# Power.net
KiCad netlist of a schematic drawn in Altium Designer
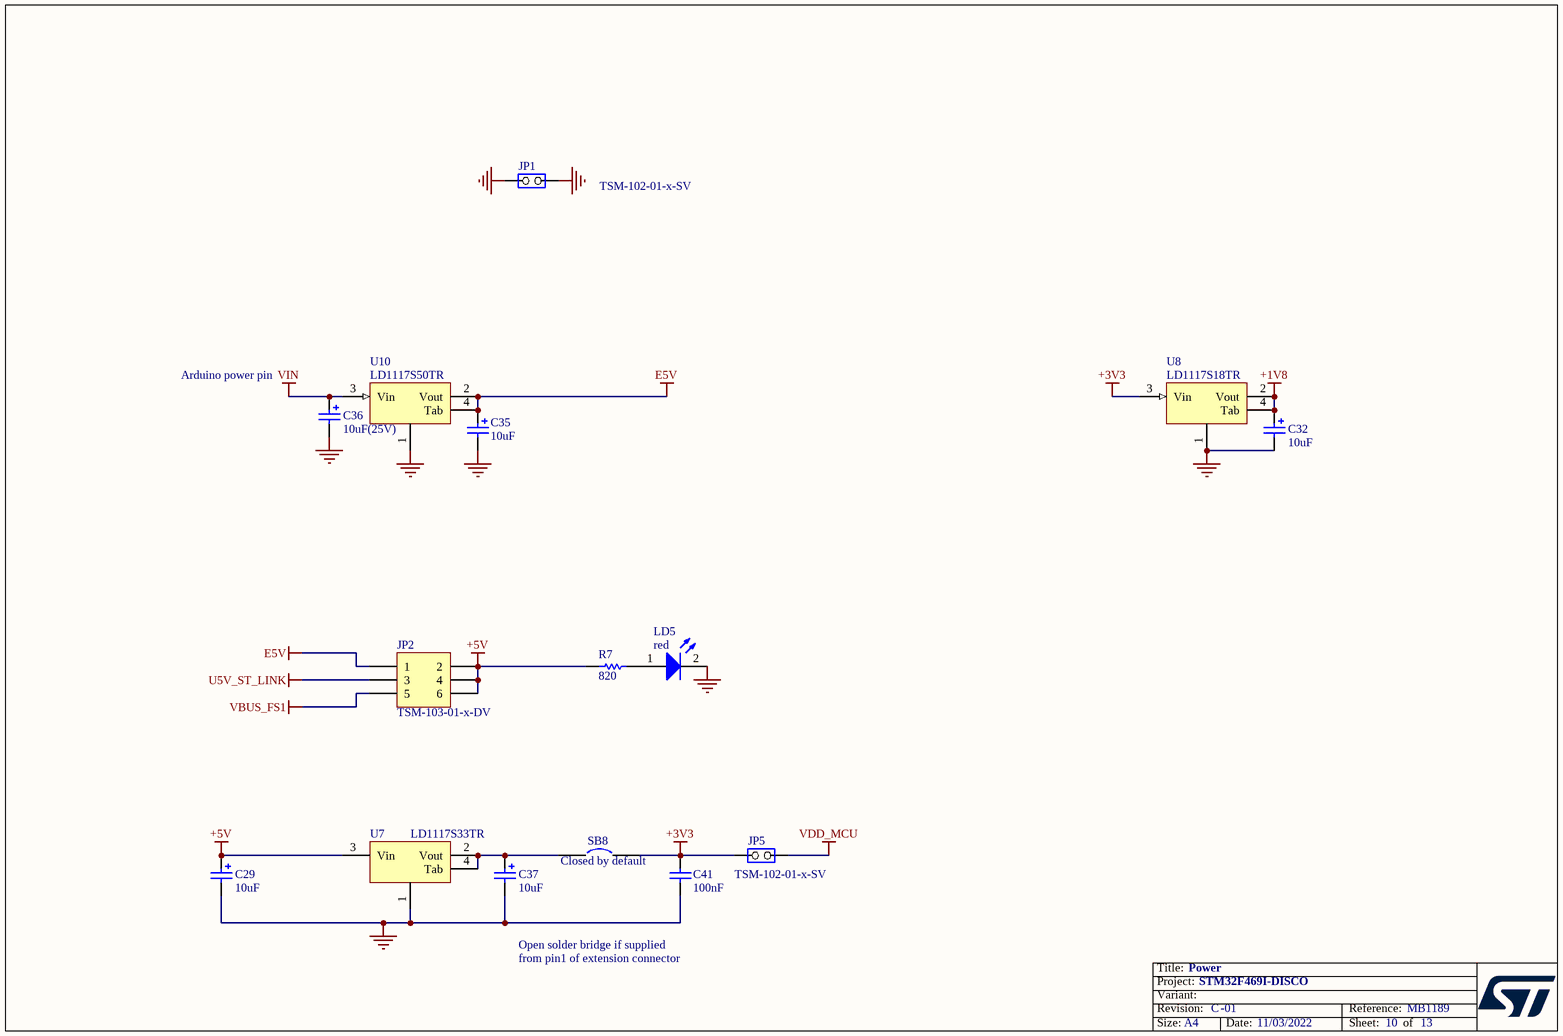
[diagram p0: Power.SchDoc]

(export (version "E")
  (design (tool "Eeschema 10.0.6"))
  (components
    (comp (ref "C29")
      (value "10uF")
      (footprint "CPOL_TAJ-A_1206_H180")
      (description "Capacitor, Tantalum, 10uF, 16V, 10%, 3Ohms, pkg Type_A (3216 metric), T=1.6mm")
      (libsource (lib "MB1189") (part "Cap_TAJA106K016R"))
    )
    (comp (ref "C32")
      (value "10uF")
      (footprint "CPOL_TAJ-A_1206_H180")
      (description "Capacitor, Tantalum, 10uF, 16V, 10%, 3Ohms, pkg Type_A (3216 metric), T=1.6mm")
      (libsource (lib "MB1189") (part "Cap_TAJA106K016R"))
    )
    (comp (ref "C35")
      (value "10uF")
      (footprint "CPOL_TAJ-A_1206_H180")
      (description "Capacitor, Tantalum, 10uF, 16V, 10%, 3Ohms, pkg Type_A (3216 metric), T=1.6mm")
      (libsource (lib "MB1189") (part "Cap_TAJA106K016R"))
    )
    (comp (ref "C36")
      (value "10uF(25V)")
      (footprint "CPOL_TAJ-B_1210_H210")
      (description "Capacitor, Tantalum, 10uF, 25V, 10%, 2.5ohms, pkg Type_B (3528 metric), T=1.9mm")
      (libsource (lib "MB1189") (part "Cap_TAJB106K025RNJ"))
    )
    (comp (ref "C37")
      (value "10uF")
      (footprint "CPOL_TAJ-A_1206_H180")
      (description "Capacitor, Tantalum, 10uF, 16V, 10%, 3Ohms, pkg Type_A (3216 metric), T=1.6mm")
      (libsource (lib "MB1189") (part "Cap_TAJA106K016R"))
    )
    (comp (ref "C41")
      (value "100nF")
      (footprint "0402C")
      (description "Capacitor")
      (fields (field (name "PUBLISHER") "Altium Limited"))
      (libsource (lib "Miscellaneous Devices") (part "Cap"))
    )
    (comp (ref "JP1")
      (value "TSM-102-01-x-SV")
      (footprint "TSM-102-01-x-SV")
      (libsource (lib "*") (part "JP2"))
    )
    (comp (ref "JP2")
      (value "TSM-103-01-x-DV")
      (footprint "TSM-103-01-x-DV")
      (description "Header, 3-Pin, Dual row")
      (fields (field (name "PUBLISHER") "Altium Limited"))
      (libsource (lib "Miscellaneous Connectors") (part "Header 3X2"))
    )
    (comp (ref "JP5")
      (value "TSM-102-01-x-SV")
      (footprint "TSM-102-01-x-SV")
      (libsource (lib "*") (part "JP2"))
    )
    (comp (ref "LD5")
      (value "red")
      (footprint "0603D")
      (description "Typical RED, GREEN, YELLOW, AMBER GaAs LED")
      (fields (field (name "PUBLISHER") "Altium Limited"))
      (libsource (lib "Miscellaneous Devices") (part "LED2"))
    )
    (comp (ref "R7")
      (value "820")
      (footprint "0603R")
      (description "Resistor")
      (fields (field (name "PUBLISHER") "Altium Limited"))
      (libsource (lib "Miscellaneous Devices") (part "res1"))
    )
    (comp (ref "SB8")
      (value "Closed by default")
      (footprint "SB_0603")
      (description "Circuit Breaker")
      (fields (field (name "PUBLISHER") "Altium Limited"))
      (libsource (lib "Miscellaneous Devices") (part "Circuit Breaker"))
    )
    (comp (ref "U7")
      (value "LD1117S33TR")
      (footprint "SOT-223")
      (description "LOW DROP FIXED AND ADJUSTABLE POSITIVE VOLTAGE REGULATORS (3.3 Volts)")
      (libsource (lib "MCD_TOOLS") (part "LD1117S33TR"))
    )
    (comp (ref "U8") (value "LD1117S18TR") (footprint "SOT-223") (libsource (lib "mb1045") (part "LD1117")))
    (comp (ref "U10") (value "LD1117S50TR") (footprint "SOT-223") (libsource (lib "mb1045") (part "LD1117")))
  )
  (nets
    (net (code "1") (name "+1V8") (class "Default")
      (node (ref "C32") (pin "1") (pinfunction "1_1") (pintype "passive"))
      (node (ref "U8") (pin "2") (pinfunction "Vout_2") (pintype "power_in"))
      (node (ref "U8") (pin "4") (pinfunction "Tab_4") (pintype "power_in"))
    )
    (net (code "2") (name "+3V3") (class "Default")
      (node (ref "C41") (pin "1") (pinfunction "1_1") (pintype "passive"))
      (node (ref "JP5") (pin "1") (pinfunction "COMMON_1") (pintype "passive"))
      (node (ref "SB8") (pin "2") (pinfunction "2_2") (pintype "passive"))
      (node (ref "U8") (pin "3") (pinfunction "Vin_3") (pintype "input"))
    )
    (net (code "3") (name "+5V") (class "Default")
      (node (ref "C29") (pin "1") (pinfunction "1_1") (pintype "passive"))
      (node (ref "JP2") (pin "2") (pinfunction "2_2") (pintype "passive"))
      (node (ref "JP2") (pin "4") (pinfunction "4_4") (pintype "passive"))
      (node (ref "JP2") (pin "6") (pinfunction "6_6") (pintype "passive"))
      (node (ref "R7") (pin "2") (pinfunction "2_2") (pintype "passive"))
      (node (ref "U7") (pin "3") (pinfunction "Vin_3") (pintype "passive"))
    )
    (net (code "4") (name "E5V") (class "Default")
      (node (ref "C35") (pin "1") (pinfunction "1_1") (pintype "passive"))
      (node (ref "JP2") (pin "1") (pinfunction "1_1") (pintype "passive"))
      (node (ref "U10") (pin "2") (pinfunction "Vout_2") (pintype "power_in"))
      (node (ref "U10") (pin "4") (pinfunction "Tab_4") (pintype "power_in"))
    )
    (net (code "5") (name "GND") (class "Default")
      (node (ref "C29") (pin "2") (pinfunction "2_2") (pintype "passive"))
      (node (ref "C32") (pin "2") (pinfunction "2_2") (pintype "passive"))
      (node (ref "C35") (pin "2") (pinfunction "2_2") (pintype "passive"))
      (node (ref "C36") (pin "2") (pinfunction "2_2") (pintype "passive"))
      (node (ref "C37") (pin "2") (pinfunction "2_2") (pintype "passive"))
      (node (ref "C41") (pin "2") (pinfunction "2_2") (pintype "passive"))
      (node (ref "JP1") (pin "1") (pinfunction "COMMON_1") (pintype "passive"))
      (node (ref "JP1") (pin "2") (pinfunction "NO_2") (pintype "passive"))
      (node (ref "LD5") (pin "2") (pinfunction "K_2") (pintype "passive"))
      (node (ref "U10") (pin "1") (pintype "passive"))
      (node (ref "U7") (pin "1") (pintype "passive"))
      (node (ref "U8") (pin "1") (pintype "passive"))
    )
    (net (code "6") (name "Net-(LD5-A)") (class "Default")
      (node (ref "LD5") (pin "1") (pinfunction "A_1") (pintype "passive"))
      (node (ref "R7") (pin "1") (pinfunction "1_1") (pintype "passive"))
    )
    (net (code "7") (name "Net-(U7-Tab)") (class "Default")
      (node (ref "C37") (pin "1") (pinfunction "1_1") (pintype "passive"))
      (node (ref "SB8") (pin "1") (pinfunction "1_1") (pintype "passive"))
      (node (ref "U7") (pin "2") (pinfunction "Vout_2") (pintype "passive"))
      (node (ref "U7") (pin "4") (pinfunction "Tab_4") (pintype "passive"))
    )
    (net (code "8") (name "U5V_ST_LINK") (class "Default")
      (node (ref "JP2") (pin "3") (pinfunction "3_3") (pintype "passive"))
    )
    (net (code "9") (name "VBUS_FS1") (class "Default")
      (node (ref "JP2") (pin "5") (pinfunction "5_5") (pintype "passive"))
    )
    (net (code "10") (name "VDD_MCU") (class "Default")
      (node (ref "JP5") (pin "2") (pinfunction "NO_2") (pintype "passive"))
    )
    (net (code "11") (name "VIN") (class "Default")
      (node (ref "C36") (pin "1") (pinfunction "1_1") (pintype "passive"))
      (node (ref "U10") (pin "3") (pinfunction "Vin_3") (pintype "input"))
    )
  )
)
